# 1_Power_Supply.net
KiCad netlist of a schematic drawn in Altium Designer
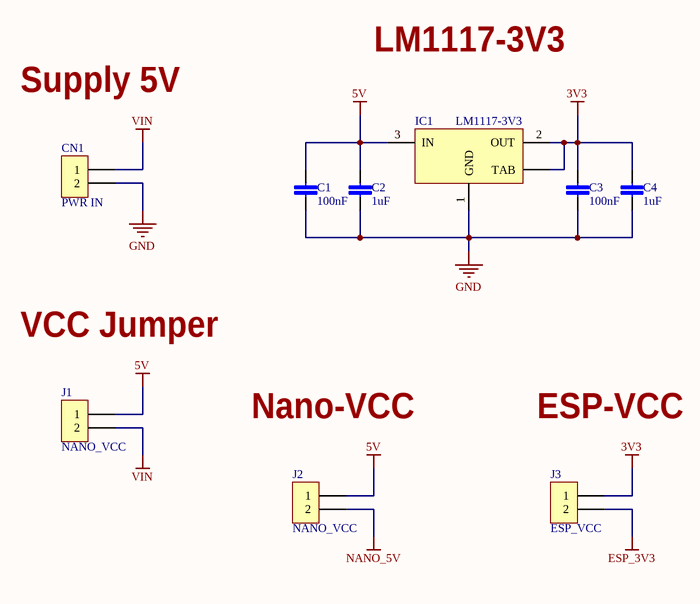
[diagram p0: 1.Power_Supply.SchDoc]

(export (version "E")
  (design (tool "Eeschema 10.0.6"))
  (components
    (comp (ref "C1")
      (value "100nF")
      (footprint "C0805")
      (description "Multilayer Ceramic Capacitors MLCC - SMD/SMT 0805 0.1uF 50volts X7R 20%")
      (fields
        (field (name "MANUFACTURER") "Murata")
        (field (name "MANUFACTURER PART NUMBER") "GCJ21BR71H104MA01L")
      )
      (libsource (lib "keri_lib") (part "C_0805_0.1uF"))
    )
    (comp (ref "C2")
      (value "1uF")
      (footprint "C0805")
      (description "Multilayer Ceramic Capacitors MLCC - SMD/SMT 0805 1uF 50volts X7R 20%")
      (fields
        (field (name "MANUFACTURER") "Murata")
        (field (name "MANUFACTURER PART NUMBER") "GCJ21BR71H105MA01L")
      )
      (libsource (lib "keri_lib") (part "C_0805_1uF"))
    )
    (comp (ref "C3")
      (value "100nF")
      (footprint "C0805")
      (description "Multilayer Ceramic Capacitors MLCC - SMD/SMT 0805 0.1uF 50volts X7R 20%")
      (fields
        (field (name "MANUFACTURER") "Murata")
        (field (name "MANUFACTURER PART NUMBER") "GCJ21BR71H104MA01L")
      )
      (libsource (lib "keri_lib") (part "C_0805_0.1uF"))
    )
    (comp (ref "C4")
      (value "1uF")
      (footprint "C0805")
      (description "Multilayer Ceramic Capacitors MLCC - SMD/SMT 0805 1uF 50volts X7R 20%")
      (fields
        (field (name "MANUFACTURER") "Murata")
        (field (name "MANUFACTURER PART NUMBER") "GCJ21BR71H105MA01L")
      )
      (libsource (lib "keri_lib") (part "C_0805_1uF"))
    )
    (comp (ref "CN1")
      (value "PWR IN")
      (footprint "Terminal_5.08mm_1X02")
      (description "Fixed Terminal Blocks TERMI-BLOK PCB")
      (fields
        (field (name "MANUFACTURER") "TE Connectivity")
        (field (name "MANUFACTURER PART NUMBER") "796682-2")
      )
      (libsource (lib "keri_lib") (part "Terminal_5.08mm_1X02"))
    )
    (comp (ref "IC1")
      (value "LM1117-3V3")
      (footprint "SOT223")
      (description "IC, LINEAR VOLTAGE REGULATOR")
      (fields
        (field (name "MANUFACTURER") "TI National Semiconductor")
        (field (name "MANUFACTURER PART NUMBER") "LM1117MPX-3.3")
      )
      (libsource (lib "keri_lib") (part "VREG_LM1117_3V3"))
    )
    (comp (ref "J1")
      (value "NANO_VCC")
      (footprint "Header_2.54mm_1X02")
      (fields
        (field (name "MANUFACTURER") "TE Connectivity")
        (field (name "MANUFACTURER PART NUMBER") "826646-2")
      )
      (libsource (lib "keri_lib") (part "Header_2.54mm_1X02"))
    )
    (comp (ref "J2")
      (value "NANO_VCC")
      (footprint "Header_2.54mm_1X02")
      (fields
        (field (name "MANUFACTURER") "TE Connectivity")
        (field (name "MANUFACTURER PART NUMBER") "826646-2")
      )
      (libsource (lib "keri_lib") (part "Header_2.54mm_1X02"))
    )
    (comp (ref "J3")
      (value "ESP_VCC")
      (footprint "Header_2.54mm_1X02")
      (fields
        (field (name "MANUFACTURER") "TE Connectivity")
        (field (name "MANUFACTURER PART NUMBER") "826646-2")
      )
      (libsource (lib "keri_lib") (part "Header_2.54mm_1X02"))
    )
  )
  (nets
    (net (code "1") (name "3V3") (class "Default")
      (node (ref "C3") (pin "1") (pinfunction "1_1") (pintype "passive"))
      (node (ref "C4") (pin "1") (pinfunction "1_1") (pintype "passive"))
      (node (ref "IC1") (pin "2") (pinfunction "OUT_2") (pintype "passive"))
      (node (ref "IC1") (pin "4") (pinfunction "TAB_4") (pintype "passive"))
      (node (ref "J3") (pin "1") (pinfunction "1_1") (pintype "passive"))
    )
    (net (code "2") (name "5V") (class "Default")
      (node (ref "C1") (pin "1") (pinfunction "1_1") (pintype "passive"))
      (node (ref "C2") (pin "1") (pinfunction "1_1") (pintype "passive"))
      (node (ref "IC1") (pin "3") (pinfunction "IN_3") (pintype "passive"))
      (node (ref "J1") (pin "1") (pinfunction "1_1") (pintype "passive"))
      (node (ref "J2") (pin "1") (pinfunction "1_1") (pintype "passive"))
    )
    (net (code "3") (name "ESP_3V3") (class "Default")
      (node (ref "J3") (pin "2") (pinfunction "2_2") (pintype "passive"))
    )
    (net (code "4") (name "GND") (class "Default")
      (node (ref "C1") (pin "2") (pinfunction "2_2") (pintype "passive"))
      (node (ref "C2") (pin "2") (pinfunction "2_2") (pintype "passive"))
      (node (ref "C3") (pin "2") (pinfunction "2_2") (pintype "passive"))
      (node (ref "C4") (pin "2") (pinfunction "2_2") (pintype "passive"))
      (node (ref "CN1") (pin "2") (pinfunction "2_2") (pintype "passive"))
      (node (ref "IC1") (pin "1") (pinfunction "GND_1") (pintype "passive"))
    )
    (net (code "5") (name "NANO_5V") (class "Default")
      (node (ref "J2") (pin "2") (pinfunction "2_2") (pintype "passive"))
    )
    (net (code "6") (name "VIN") (class "Default")
      (node (ref "CN1") (pin "1") (pinfunction "1_1") (pintype "passive"))
      (node (ref "J1") (pin "2") (pinfunction "2_2") (pintype "passive"))
    )
  )
)
